# THB7128.net
KiCad netlist of a schematic drawn in Altium Designer
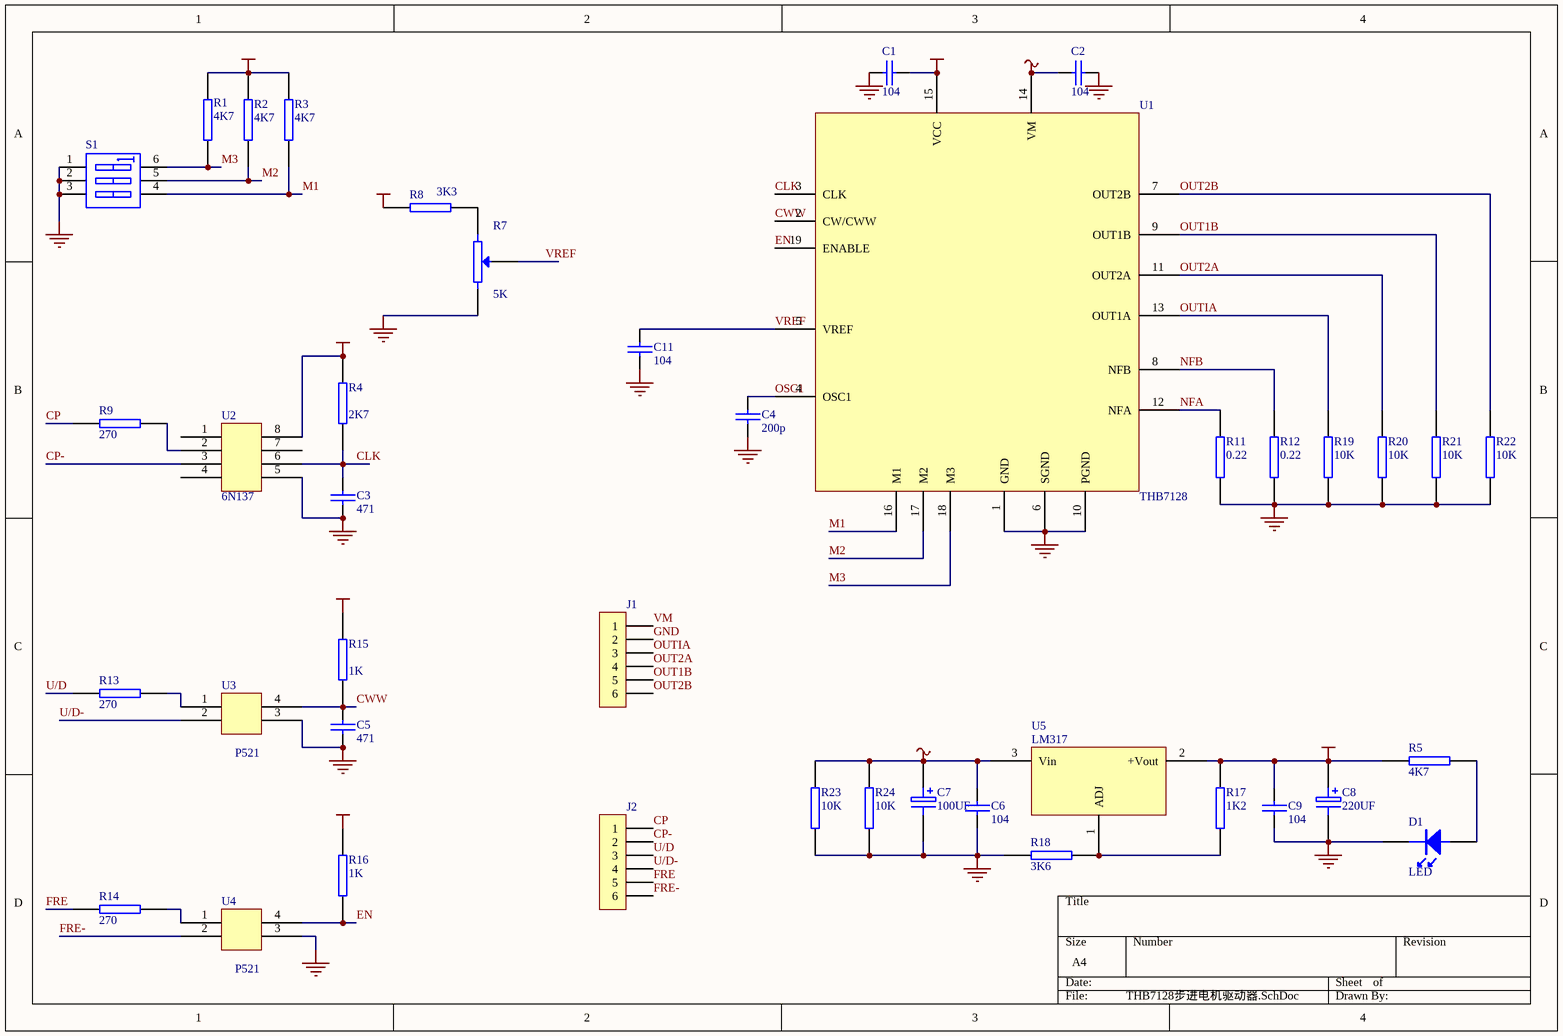
[diagram p0: THB7128步进电机驱动器.SchDoc]

(export (version "E")
  (design (tool "Eeschema 10.0.6"))
  (components
    (comp (ref "C1")
      (value "104")
      (footprint "0805")
      (description "Capacitor")
      (libsource (lib "*") (part "CAP"))
    )
    (comp (ref "C2")
      (value "104")
      (footprint "0805")
      (description "Capacitor")
      (libsource (lib "*") (part "CAP"))
    )
    (comp (ref "C3")
      (value "471")
      (footprint "0805")
      (description "Capacitor")
      (libsource (lib "*") (part "CAP"))
    )
    (comp (ref "C4")
      (value "200p")
      (footprint "0805")
      (description "Capacitor")
      (libsource (lib "*") (part "CAP"))
    )
    (comp (ref "C5")
      (value "471")
      (footprint "0805")
      (description "Capacitor")
      (libsource (lib "*") (part "CAP"))
    )
    (comp (ref "C6")
      (value "104")
      (footprint "0805")
      (description "Capacitor")
      (libsource (lib "*") (part "CAP"))
    )
    (comp (ref "C7")
      (value "100UF")
      (footprint "C300")
      (description "Electrolytic Capacitor")
      (libsource (lib "*") (part "ELECTRO1"))
    )
    (comp (ref "C8")
      (value "220UF")
      (footprint "C300")
      (description "Electrolytic Capacitor")
      (libsource (lib "*") (part "ELECTRO1"))
    )
    (comp (ref "C9")
      (value "104")
      (footprint "0805")
      (description "Capacitor")
      (libsource (lib "*") (part "CAP"))
    )
    (comp (ref "C11")
      (value "104")
      (footprint "0805")
      (description "Capacitor")
      (libsource (lib "*") (part "CAP"))
    )
    (comp (ref "D1") (value "LED") (footprint "RD") (libsource (lib "*") (part "LED")))
    (comp (ref "J1")
      (value "~")
      (footprint "POW6")
      (description "Connector")
      (libsource (lib "*") (part "CON6"))
    )
    (comp (ref "J2")
      (value "~")
      (footprint "POW6")
      (description "Connector")
      (libsource (lib "*") (part "CON6"))
    )
    (comp (ref "R1") (value "4K7") (footprint "0805") (libsource (lib "*") (part "RES2")))
    (comp (ref "R2") (value "4K7") (footprint "0805") (libsource (lib "*") (part "RES2")))
    (comp (ref "R3") (value "4K7") (footprint "0805") (libsource (lib "*") (part "RES2")))
    (comp (ref "R4") (value "2K7") (footprint "0805") (libsource (lib "*") (part "RES2")))
    (comp (ref "R5") (value "4K7") (footprint "0805") (libsource (lib "*") (part "RES2")))
    (comp (ref "R7")
      (value "5K")
      (footprint "RE")
      (description "Potentiometer")
      (libsource (lib "*") (part "POT2"))
    )
    (comp (ref "R8") (value "3K3") (footprint "0805") (libsource (lib "*") (part "RES2")))
    (comp (ref "R9") (value "270") (footprint "0805") (libsource (lib "*") (part "RES2")))
    (comp (ref "R11") (value "0.22") (footprint "2512") (libsource (lib "*") (part "RES2")))
    (comp (ref "R12") (value "0.22") (footprint "2512") (libsource (lib "*") (part "RES2")))
    (comp (ref "R13") (value "270") (footprint "0805") (libsource (lib "*") (part "RES2")))
    (comp (ref "R14") (value "270") (footprint "0805") (libsource (lib "*") (part "RES2")))
    (comp (ref "R15") (value "1K") (footprint "0805") (libsource (lib "*") (part "RES2")))
    (comp (ref "R16") (value "1K") (footprint "0805") (libsource (lib "*") (part "RES2")))
    (comp (ref "R17") (value "1K2") (footprint "0805") (libsource (lib "*") (part "RES2")))
    (comp (ref "R18") (value "3K6") (footprint "0805") (libsource (lib "*") (part "RES2")))
    (comp (ref "R19") (value "10K") (footprint "0805") (libsource (lib "*") (part "RES2")))
    (comp (ref "R20") (value "10K") (footprint "0805") (libsource (lib "*") (part "RES2")))
    (comp (ref "R21") (value "10K") (footprint "0805") (libsource (lib "*") (part "RES2")))
    (comp (ref "R22") (value "10K") (footprint "0805") (libsource (lib "*") (part "RES2")))
    (comp (ref "R23") (value "10K") (footprint "0805") (libsource (lib "*") (part "RES2")))
    (comp (ref "R24") (value "10K") (footprint "0805") (libsource (lib "*") (part "RES2")))
    (comp (ref "S1")
      (value "~")
      (footprint "DIP6")
      (description "DIP Switch")
      (libsource (lib "*") (part "SW DIP-3"))
    )
    (comp (ref "U1") (value "THB7128") (footprint "ZIP19") (libsource (lib "*") (part "THB7128-V2")))
    (comp (ref "U2") (value "6N137") (footprint "DIP8") (libsource (lib "*") (part "DIP8")))
    (comp (ref "U3") (value "P521") (footprint "DIP4") (libsource (lib "*") (part "DIP4")))
    (comp (ref "U4") (value "P521") (footprint "DIP4") (libsource (lib "*") (part "DIP4")))
    (comp (ref "U5") (value "LM317") (footprint "252") (libsource (lib "*") (part "LM117T")))
  )
  (nets
    (net (code "1") (name "/CLK") (class "Default")
      (node (ref "C3") (pin "2") (pinfunction "2_2") (pintype "passive"))
      (node (ref "R4") (pin "2") (pinfunction "2_2") (pintype "passive"))
      (node (ref "U1") (pin "3") (pinfunction "CLK_3") (pintype "passive"))
      (node (ref "U2") (pin "6") (pintype "passive"))
    )
    (net (code "2") (name "/CP") (class "Default")
      (node (ref "J2") (pin "1") (pinfunction "1_1") (pintype "passive"))
      (node (ref "R9") (pin "1") (pinfunction "1_1") (pintype "passive"))
    )
    (net (code "3") (name "/CP-") (class "Default")
      (node (ref "J2") (pin "2") (pinfunction "2_2") (pintype "passive"))
      (node (ref "U2") (pin "3") (pintype "passive"))
    )
    (net (code "4") (name "/CWW") (class "Default")
      (node (ref "C5") (pin "1") (pinfunction "1_1") (pintype "passive"))
      (node (ref "R15") (pin "1") (pinfunction "1_1") (pintype "passive"))
      (node (ref "U1") (pin "2") (pinfunction "CW/CWW_2") (pintype "passive"))
      (node (ref "U3") (pin "4") (pintype "passive"))
    )
    (net (code "5") (name "/EN") (class "Default")
      (node (ref "R16") (pin "1") (pinfunction "1_1") (pintype "passive"))
      (node (ref "U1") (pin "19") (pinfunction "ENABLE_19") (pintype "passive"))
      (node (ref "U4") (pin "4") (pintype "passive"))
    )
    (net (code "6") (name "/FRE") (class "Default")
      (node (ref "J2") (pin "5") (pinfunction "5_5") (pintype "passive"))
      (node (ref "R14") (pin "1") (pinfunction "1_1") (pintype "passive"))
    )
    (net (code "7") (name "/FRE-") (class "Default")
      (node (ref "J2") (pin "6") (pinfunction "6_6") (pintype "passive"))
      (node (ref "U4") (pin "2") (pintype "passive"))
    )
    (net (code "8") (name "/M1") (class "Default")
      (node (ref "R3") (pin "1") (pinfunction "1_1") (pintype "passive"))
      (node (ref "S1") (pin "4") (pinfunction "B3_4") (pintype "passive"))
      (node (ref "U1") (pin "16") (pinfunction "M1_16") (pintype "passive"))
    )
    (net (code "9") (name "/M2") (class "Default")
      (node (ref "R2") (pin "1") (pinfunction "1_1") (pintype "passive"))
      (node (ref "S1") (pin "5") (pinfunction "B2_5") (pintype "passive"))
      (node (ref "U1") (pin "17") (pinfunction "M2_17") (pintype "passive"))
    )
    (net (code "10") (name "/M3") (class "Default")
      (node (ref "R1") (pin "1") (pinfunction "1_1") (pintype "passive"))
      (node (ref "S1") (pin "6") (pinfunction "B1_6") (pintype "passive"))
      (node (ref "U1") (pin "18") (pinfunction "M3_18") (pintype "passive"))
    )
    (net (code "11") (name "/NFA") (class "Default")
      (node (ref "R11") (pin "1") (pinfunction "1_1") (pintype "passive"))
      (node (ref "U1") (pin "12") (pinfunction "NFA_12") (pintype "passive"))
    )
    (net (code "12") (name "/NFB") (class "Default")
      (node (ref "R12") (pin "1") (pinfunction "1_1") (pintype "passive"))
      (node (ref "U1") (pin "8") (pinfunction "NFB_8") (pintype "passive"))
    )
    (net (code "13") (name "/OSC1") (class "Default")
      (node (ref "C4") (pin "1") (pinfunction "1_1") (pintype "passive"))
      (node (ref "U1") (pin "4") (pinfunction "OSC1_4") (pintype "passive"))
    )
    (net (code "14") (name "/OUT1B") (class "Default")
      (node (ref "J1") (pin "5") (pinfunction "5_5") (pintype "passive"))
      (node (ref "R21") (pin "2") (pinfunction "2_2") (pintype "passive"))
      (node (ref "U1") (pin "9") (pinfunction "OUT1B_9") (pintype "passive"))
    )
    (net (code "15") (name "/OUT2A") (class "Default")
      (node (ref "J1") (pin "4") (pinfunction "4_4") (pintype "passive"))
      (node (ref "R20") (pin "2") (pinfunction "2_2") (pintype "passive"))
      (node (ref "U1") (pin "11") (pinfunction "OUT2A_11") (pintype "passive"))
    )
    (net (code "16") (name "/OUT2B") (class "Default")
      (node (ref "J1") (pin "6") (pinfunction "6_6") (pintype "passive"))
      (node (ref "R22") (pin "2") (pinfunction "2_2") (pintype "passive"))
      (node (ref "U1") (pin "7") (pinfunction "OUT2B_7") (pintype "passive"))
    )
    (net (code "17") (name "/OUTIA") (class "Default")
      (node (ref "J1") (pin "3") (pinfunction "3_3") (pintype "passive"))
      (node (ref "R19") (pin "2") (pinfunction "2_2") (pintype "passive"))
      (node (ref "U1") (pin "13") (pinfunction "OUT1A_13") (pintype "passive"))
    )
    (net (code "18") (name "/U{slash}D") (class "Default")
      (node (ref "J2") (pin "3") (pinfunction "3_3") (pintype "passive"))
      (node (ref "R13") (pin "1") (pinfunction "1_1") (pintype "passive"))
    )
    (net (code "19") (name "/U{slash}D-") (class "Default")
      (node (ref "J2") (pin "4") (pinfunction "4_4") (pintype "passive"))
      (node (ref "U3") (pin "2") (pintype "passive"))
    )
    (net (code "20") (name "/VREF") (class "Default")
      (node (ref "C11") (pin "1") (pinfunction "1_1") (pintype "passive"))
      (node (ref "R7") (pin "3") (pinfunction "W_3") (pintype "passive"))
      (node (ref "U1") (pin "5") (pinfunction "VREF_5") (pintype "passive"))
    )
    (net (code "21") (name "GND") (class "Default")
      (node (ref "C1") (pin "1") (pinfunction "1_1") (pintype "passive"))
      (node (ref "C11") (pin "2") (pinfunction "2_2") (pintype "passive"))
      (node (ref "C2") (pin "2") (pinfunction "2_2") (pintype "passive"))
      (node (ref "C3") (pin "1") (pinfunction "1_1") (pintype "passive"))
      (node (ref "C4") (pin "2") (pinfunction "2_2") (pintype "passive"))
      (node (ref "C5") (pin "2") (pinfunction "2_2") (pintype "passive"))
      (node (ref "C6") (pin "2") (pinfunction "2_2") (pintype "passive"))
      (node (ref "C7") (pin "2") (pinfunction "2_2") (pintype "passive"))
      (node (ref "C8") (pin "2") (pinfunction "2_2") (pintype "passive"))
      (node (ref "C9") (pin "2") (pinfunction "2_2") (pintype "passive"))
      (node (ref "D1") (pin "K") (pinfunction "2_K") (pintype "passive"))
      (node (ref "J1") (pin "2") (pinfunction "2_2") (pintype "passive"))
      (node (ref "R11") (pin "2") (pinfunction "2_2") (pintype "passive"))
      (node (ref "R12") (pin "2") (pinfunction "2_2") (pintype "passive"))
      (node (ref "R18") (pin "2") (pinfunction "2_2") (pintype "passive"))
      (node (ref "R19") (pin "1") (pinfunction "1_1") (pintype "passive"))
      (node (ref "R20") (pin "1") (pinfunction "1_1") (pintype "passive"))
      (node (ref "R21") (pin "1") (pinfunction "1_1") (pintype "passive"))
      (node (ref "R22") (pin "1") (pinfunction "1_1") (pintype "passive"))
      (node (ref "R23") (pin "1") (pinfunction "1_1") (pintype "passive"))
      (node (ref "R24") (pin "1") (pinfunction "1_1") (pintype "passive"))
      (node (ref "R7") (pin "2") (pinfunction "2_2") (pintype "passive"))
      (node (ref "S1") (pin "1") (pinfunction "A1_1") (pintype "passive"))
      (node (ref "S1") (pin "2") (pinfunction "A2_2") (pintype "passive"))
      (node (ref "S1") (pin "3") (pinfunction "A3_3") (pintype "passive"))
      (node (ref "U1") (pin "1") (pinfunction "GND_1") (pintype "passive"))
      (node (ref "U1") (pin "10") (pinfunction "PGND_10") (pintype "passive"))
      (node (ref "U1") (pin "6") (pinfunction "SGND_6") (pintype "passive"))
      (node (ref "U2") (pin "5") (pintype "passive"))
      (node (ref "U3") (pin "3") (pintype "passive"))
      (node (ref "U4") (pin "3") (pintype "passive"))
    )
    (net (code "22") (name "Net-(D1-1)") (class "Default")
      (node (ref "D1") (pin "A") (pinfunction "1_A") (pintype "passive"))
      (node (ref "R5") (pin "1") (pinfunction "1_1") (pintype "passive"))
    )
    (net (code "23") (name "Net-(R7-Pad1)") (class "Default")
      (node (ref "R7") (pin "1") (pinfunction "1_1") (pintype "passive"))
      (node (ref "R8") (pin "1") (pinfunction "1_1") (pintype "passive"))
    )
    (net (code "24") (name "Net-(R9-Pad2)") (class "Default")
      (node (ref "R9") (pin "2") (pinfunction "2_2") (pintype "passive"))
      (node (ref "U2") (pin "2") (pintype "passive"))
    )
    (net (code "25") (name "Net-(R13-Pad2)") (class "Default")
      (node (ref "R13") (pin "2") (pinfunction "2_2") (pintype "passive"))
      (node (ref "U3") (pin "1") (pintype "passive"))
    )
    (net (code "26") (name "Net-(R14-Pad2)") (class "Default")
      (node (ref "R14") (pin "2") (pinfunction "2_2") (pintype "passive"))
      (node (ref "U4") (pin "1") (pintype "passive"))
    )
    (net (code "27") (name "Net-(U5-ADJ)") (class "Default")
      (node (ref "R17") (pin "2") (pinfunction "2_2") (pintype "passive"))
      (node (ref "R18") (pin "1") (pinfunction "1_1") (pintype "passive"))
      (node (ref "U5") (pin "1") (pinfunction "ADJ_1") (pintype "passive"))
    )
    (net (code "28") (name "VCC") (class "Default")
      (node (ref "C1") (pin "2") (pinfunction "2_2") (pintype "passive"))
      (node (ref "C8") (pin "1") (pinfunction "1_1") (pintype "passive"))
      (node (ref "C9") (pin "1") (pinfunction "1_1") (pintype "passive"))
      (node (ref "R1") (pin "2") (pinfunction "2_2") (pintype "passive"))
      (node (ref "R15") (pin "2") (pinfunction "2_2") (pintype "passive"))
      (node (ref "R16") (pin "2") (pinfunction "2_2") (pintype "passive"))
      (node (ref "R17") (pin "1") (pinfunction "1_1") (pintype "passive"))
      (node (ref "R2") (pin "2") (pinfunction "2_2") (pintype "passive"))
      (node (ref "R3") (pin "2") (pinfunction "2_2") (pintype "passive"))
      (node (ref "R4") (pin "1") (pinfunction "1_1") (pintype "passive"))
      (node (ref "R5") (pin "2") (pinfunction "2_2") (pintype "passive"))
      (node (ref "R8") (pin "2") (pinfunction "2_2") (pintype "passive"))
      (node (ref "U1") (pin "15") (pinfunction "VCC_15") (pintype "passive"))
      (node (ref "U2") (pin "8") (pintype "passive"))
      (node (ref "U5") (pin "2") (pinfunction "+Vout_2") (pintype "passive"))
    )
    (net (code "29") (name "VM") (class "Default")
      (node (ref "C2") (pin "1") (pinfunction "1_1") (pintype "passive"))
      (node (ref "C6") (pin "1") (pinfunction "1_1") (pintype "passive"))
      (node (ref "C7") (pin "1") (pinfunction "1_1") (pintype "passive"))
      (node (ref "J1") (pin "1") (pinfunction "1_1") (pintype "passive"))
      (node (ref "R23") (pin "2") (pinfunction "2_2") (pintype "passive"))
      (node (ref "R24") (pin "2") (pinfunction "2_2") (pintype "passive"))
      (node (ref "U1") (pin "14") (pinfunction "VM_14") (pintype "passive"))
      (node (ref "U5") (pin "3") (pinfunction "Vin_3") (pintype "passive"))
    )
    (net (code "30") (name "unconnected-(U2-Pad1)") (class "Default")
      (node (ref "U2") (pin "1") (pintype "passive"))
    )
    (net (code "31") (name "unconnected-(U2-Pad4)") (class "Default")
      (node (ref "U2") (pin "4") (pintype "passive"))
    )
    (net (code "32") (name "unconnected-(U2-Pad7)") (class "Default")
      (node (ref "U2") (pin "7") (pintype "passive"))
    )
  )
)
